# arduino_miniuno.net
KiCad netlist of a schematic drawn in EAGLE
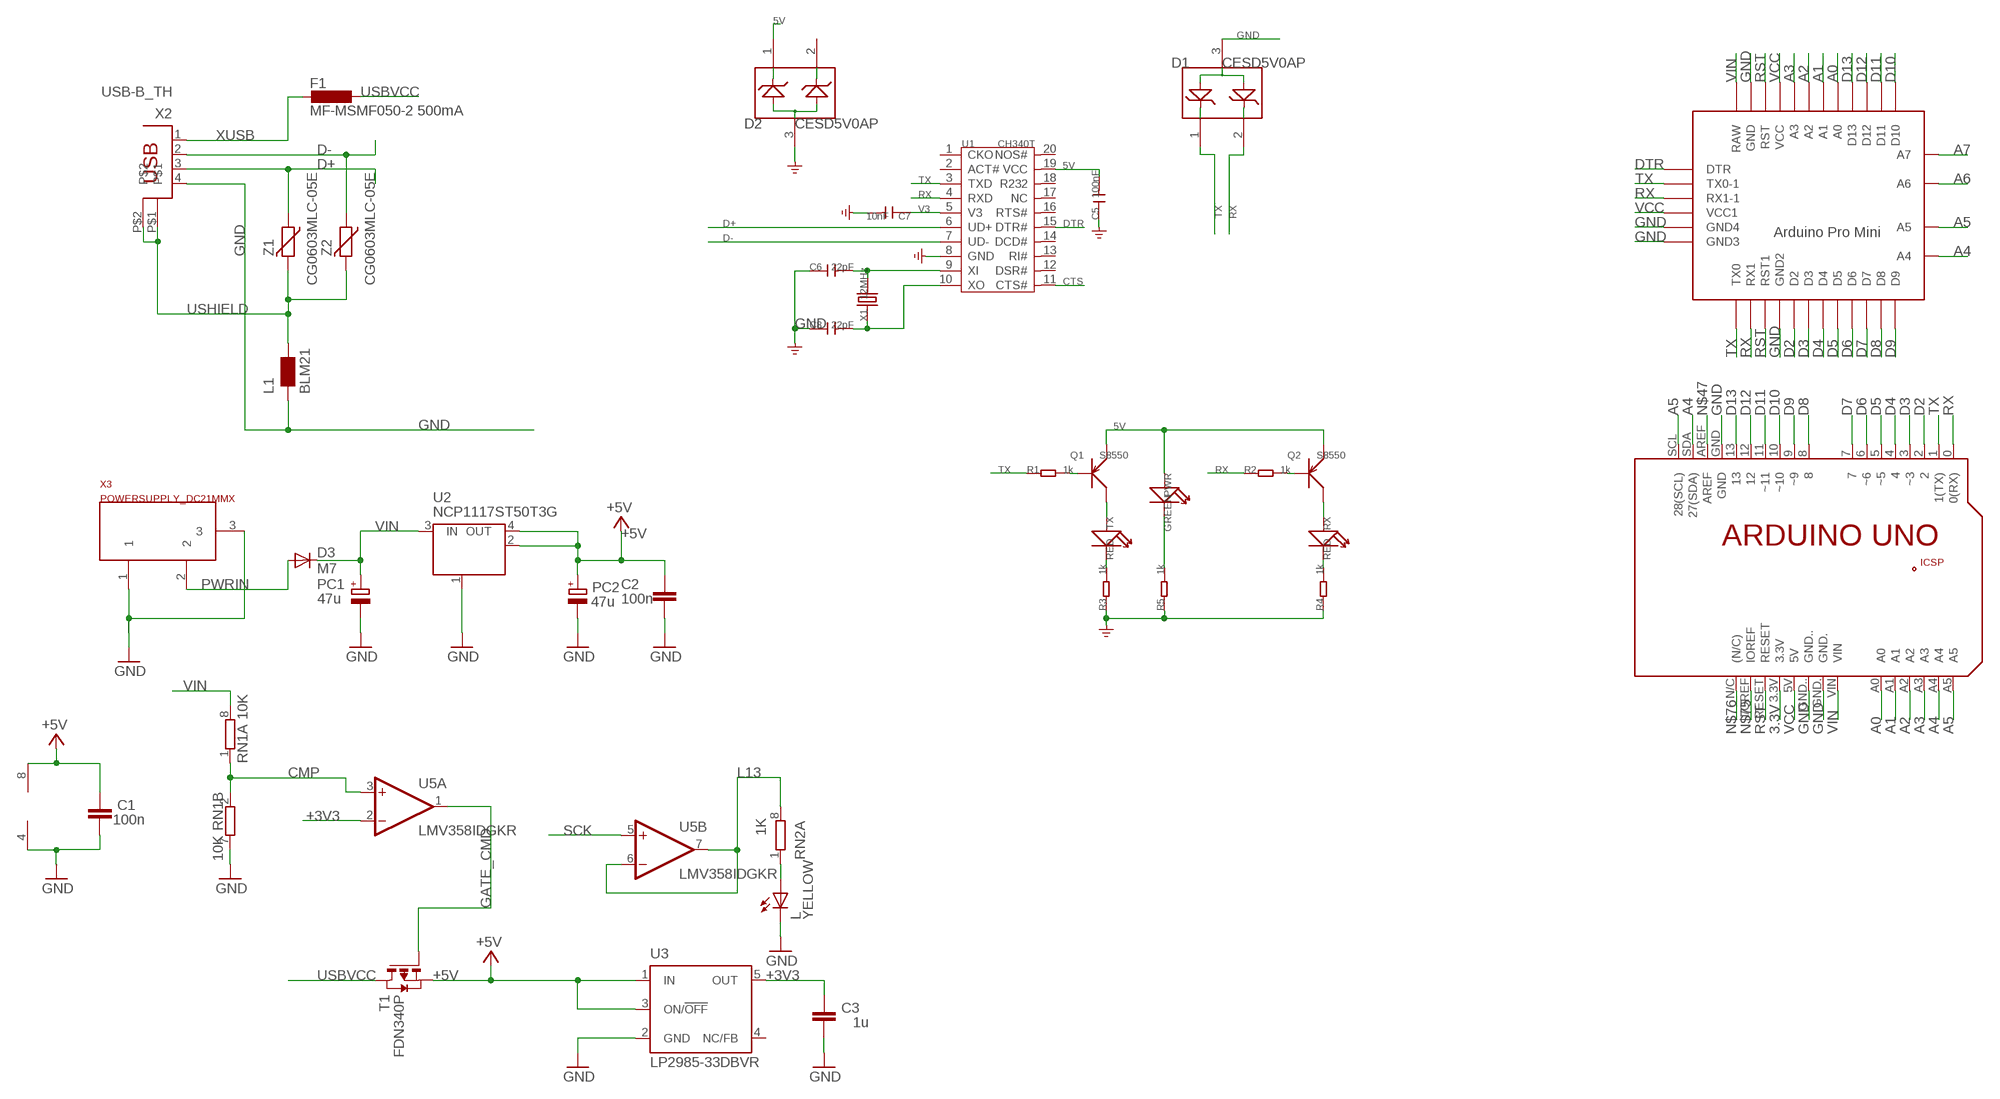
[diagram p0: schematic, sheet 1]

(export (version "E")
  (design (tool "Eeschema 10.0.6"))
  (components
    (comp (ref "C1")
      (value "100n")
      (footprint "eagle-import:C0603-ROUND")
      (libsource (lib "eagle-import") (part "C-EU0603-RND"))
    )
    (comp (ref "C2")
      (value "100n")
      (footprint "eagle-import:C0603-ROUND")
      (libsource (lib "eagle-import") (part "C-EU0603-RND"))
    )
    (comp (ref "C3")
      (value "1u")
      (footprint "eagle-import:C0603-ROUND")
      (libsource (lib "eagle-import") (part "C-EU0603-RND"))
    )
    (comp (ref "C5")
      (value "100nF")
      (footprint "eagle-import:C0402")
      (libsource (lib "eagle-import") (part "C-0402"))
    )
    (comp (ref "C6")
      (value "22pF")
      (footprint "eagle-import:C0402")
      (libsource (lib "eagle-import") (part "C-0402"))
    )
    (comp (ref "C7")
      (value "10nF")
      (footprint "eagle-import:C0402")
      (libsource (lib "eagle-import") (part "C-0402"))
    )
    (comp (ref "C8")
      (value "22pF")
      (footprint "eagle-import:C0402")
      (libsource (lib "eagle-import") (part "C-0402"))
    )
    (comp (ref "D1")
      (value "CESD5V0AP")
      (footprint "eagle-import:SOT23")
      (libsource (lib "eagle-import") (part "D-ESD-3P"))
    )
    (comp (ref "D2")
      (value "CESD5V0AP")
      (footprint "eagle-import:SOT23")
      (libsource (lib "eagle-import") (part "D-ESD-3P"))
    )
    (comp (ref "D3")
      (value "M7")
      (footprint "eagle-import:SMB")
      (libsource (lib "eagle-import") (part "DIODE-SMB"))
    )
    (comp (ref "F1")
      (value "MF-MSMF050-2 500mA")
      (footprint "eagle-import:L1812")
      (libsource (lib "eagle-import") (part "L-EUL1812"))
    )
    (comp (ref "L")
      (value "YELLOW")
      (footprint "eagle-import:CHIP-LED0805")
      (libsource (lib "eagle-import") (part "LEDCHIP-LED0805"))
    )
    (comp (ref "L1")
      (value "BLM21")
      (footprint "eagle-import:0805")
      (libsource (lib "eagle-import") (part "WE-CBF_0805"))
    )
    (comp (ref "PC1")
      (value "47u")
      (footprint "eagle-import:PANASONIC_D")
      (libsource (lib "eagle-import") (part "CPOL-EUD"))
    )
    (comp (ref "PC2")
      (value "47u")
      (footprint "eagle-import:PANASONIC_D")
      (libsource (lib "eagle-import") (part "CPOL-EUD"))
    )
    (comp (ref "PCB1")
      (value "ARDUINO_UNO")
      (footprint "eagle-import:ARDUINO_UNO")
      (libsource (lib "eagle-import") (part "ARDUINO_UNO"))
    )
    (comp (ref "PWR")
      (value "GREEN")
      (footprint "eagle-import:LED-0603")
      (libsource (lib "eagle-import") (part "LED'0603'"))
    )
    (comp (ref "Q1")
      (value "S8550")
      (footprint "eagle-import:SOT23")
      (libsource (lib "eagle-import") (part "TRANSISTOR-PNP-SOT23"))
    )
    (comp (ref "Q2")
      (value "S8550")
      (footprint "eagle-import:SOT23")
      (libsource (lib "eagle-import") (part "TRANSISTOR-PNP-SOT23"))
    )
    (comp (ref "R1")
      (value "1k")
      (footprint "eagle-import:R0402")
      (libsource (lib "eagle-import") (part "R-0402"))
    )
    (comp (ref "R2")
      (value "1k")
      (footprint "eagle-import:R0402")
      (libsource (lib "eagle-import") (part "R-0402"))
    )
    (comp (ref "R3")
      (value "1k")
      (footprint "eagle-import:R0402")
      (libsource (lib "eagle-import") (part "R-0402"))
    )
    (comp (ref "R4")
      (value "1k")
      (footprint "eagle-import:R0402")
      (libsource (lib "eagle-import") (part "R-0402"))
    )
    (comp (ref "R5")
      (value "1k")
      (footprint "eagle-import:R0402")
      (libsource (lib "eagle-import") (part "R-0402"))
    )
    (comp (ref "RN1")
      (value "10K")
      (footprint "eagle-import:CAY16")
      (libsource (lib "eagle-import") (part "4R-NCAY16"))
    )
    (comp (ref "RN2")
      (value "1K")
      (footprint "eagle-import:CAY16")
      (libsource (lib "eagle-import") (part "4R-NCAY16"))
    )
    (comp (ref "RX")
      (value "RED")
      (footprint "eagle-import:LED-0603")
      (libsource (lib "eagle-import") (part "LED'0603'"))
    )
    (comp (ref "T1")
      (value "FDN340P")
      (footprint "eagle-import:SOT-23")
      (libsource (lib "eagle-import") (part "PMOSSOT23"))
    )
    (comp (ref "TX")
      (value "RED")
      (footprint "eagle-import:LED-0603")
      (libsource (lib "eagle-import") (part "LED'0603'"))
    )
    (comp (ref "U$3")
      (value "PRO-MINI-2")
      (footprint "eagle-import:PRO-MINI-2")
      (libsource (lib "eagle-import") (part "PRO-MINI-2"))
    )
    (comp (ref "U1")
      (value "CH340T")
      (footprint "eagle-import:SSOP20")
      (libsource (lib "eagle-import") (part "CH340T"))
    )
    (comp (ref "U2")
      (value "NCP1117ST50T3G")
      (footprint "eagle-import:SOT223")
      (libsource (lib "eagle-import") (part "MC33269ST-3.3T3"))
    )
    (comp (ref "U3")
      (value "LP2985-33DBVR")
      (footprint "eagle-import:SOT23-DBV")
      (libsource (lib "eagle-import") (part "LP2985-XXDBVR33"))
    )
    (comp (ref "U5")
      (value "LMV358IDGKR")
      (footprint "eagle-import:MSOP08")
      (libsource (lib "eagle-import") (part "LMV358?MMX"))
    )
    (comp (ref "X1")
      (value "12MHz")
      (footprint "eagle-import:HC49UP")
      (libsource (lib "eagle-import") (part "CRYSTAL'HC49UP'"))
    )
    (comp (ref "X2")
      (value "USB-B_TH")
      (footprint "eagle-import:PN61729")
      (libsource (lib "eagle-import") (part "PN61729"))
    )
    (comp (ref "X3")
      (value "POWERSUPPLY_DC21MMX")
      (footprint "eagle-import:POWERSUPPLY_DC-21MM")
      (libsource (lib "eagle-import") (part "POWERSUPPLY_DC21MMX"))
    )
    (comp (ref "Z1")
      (value "CG0603MLC-05E")
      (footprint "eagle-import:CT_CN0603")
      (libsource (lib "eagle-import") (part "VARISTORCN0603"))
    )
    (comp (ref "Z2")
      (value "CG0603MLC-05E")
      (footprint "eagle-import:CT_CN0603")
      (libsource (lib "eagle-import") (part "VARISTORCN0603"))
    )
  )
  (nets
    (net (code "1") (name "+5V") (class "Default")
      (node (ref "C1") (pin "2") (pinfunction "2_2") (pintype "passive"))
      (node (ref "C2") (pin "2") (pinfunction "2_2") (pintype "passive"))
      (node (ref "PC2") (pin "+") (pinfunction "+_+") (pintype "passive"))
      (node (ref "T1") (pin "2") (pinfunction "S_2") (pintype "passive"))
      (node (ref "U2") (pin "2") (pinfunction "OUT_2") (pintype "passive"))
      (node (ref "U2") (pin "4") (pinfunction "OUT_4") (pintype "passive"))
      (node (ref "U3") (pin "1") (pinfunction "IN_1") (pintype "input"))
      (node (ref "U3") (pin "3") (pinfunction "ON/~{OFF}_3") (pintype "input"))
      (node (ref "U5") (pin "8") (pinfunction "V+_8") (pintype "power_in"))
    )
    (net (code "2") (name "/+3V3") (class "Default")
      (node (ref "C3") (pin "2") (pinfunction "2_2") (pintype "passive"))
      (node (ref "U3") (pin "5") (pinfunction "OUT_5") (pintype "passive"))
      (node (ref "U5") (pin "2") (pinfunction "-IN_2") (pintype "input"))
    )
    (net (code "3") (name "/3.3V") (class "Default")
      (node (ref "PCB1") (pin "3.3V") (pinfunction "3.3V_3.3V") (pintype "bidirectional"))
    )
    (net (code "4") (name "/5V") (class "Default")
      (node (ref "C5") (pin "2") (pinfunction "2_2") (pintype "passive"))
      (node (ref "D2") (pin "1") (pinfunction "1_1") (pintype "bidirectional"))
      (node (ref "PWR") (pin "+") (pinfunction "+_+") (pintype "passive"))
      (node (ref "Q1") (pin "2") (pinfunction "E_2") (pintype "passive"))
      (node (ref "Q2") (pin "2") (pinfunction "E_2") (pintype "passive"))
      (node (ref "U1") (pin "19") (pinfunction "VCC_19") (pintype "power_in"))
    )
    (net (code "5") (name "/A0") (class "Default")
      (node (ref "PCB1") (pin "A0") (pinfunction "A0_A0") (pintype "bidirectional"))
      (node (ref "U$3") (pin "A0") (pinfunction "A0_A0") (pintype "bidirectional"))
    )
    (net (code "6") (name "/A1") (class "Default")
      (node (ref "PCB1") (pin "A1") (pinfunction "A1_A1") (pintype "bidirectional"))
      (node (ref "U$3") (pin "A1") (pinfunction "A1_A1") (pintype "bidirectional"))
    )
    (net (code "7") (name "/A2") (class "Default")
      (node (ref "PCB1") (pin "A2") (pinfunction "A2_A2") (pintype "bidirectional"))
      (node (ref "U$3") (pin "A2") (pinfunction "A2_A2") (pintype "bidirectional"))
    )
    (net (code "8") (name "/A3") (class "Default")
      (node (ref "PCB1") (pin "A3") (pinfunction "A3_A3") (pintype "bidirectional"))
      (node (ref "U$3") (pin "A3") (pinfunction "A3_A3") (pintype "bidirectional"))
    )
    (net (code "9") (name "/A4") (class "Default")
      (node (ref "PCB1") (pin "A4") (pinfunction "A4_A4") (pintype "bidirectional"))
      (node (ref "PCB1") (pin "SDA") (pinfunction "27(SDA)_SDA") (pintype "bidirectional"))
      (node (ref "U$3") (pin "A4") (pinfunction "A4_A4") (pintype "bidirectional"))
    )
    (net (code "10") (name "/A5") (class "Default")
      (node (ref "PCB1") (pin "A5") (pinfunction "A5_A5") (pintype "bidirectional"))
      (node (ref "PCB1") (pin "SCL") (pinfunction "28(SCL)_SCL") (pintype "bidirectional"))
      (node (ref "U$3") (pin "A5") (pinfunction "A5_A5") (pintype "bidirectional"))
    )
    (net (code "11") (name "/A6") (class "Default")
      (node (ref "U$3") (pin "A6") (pinfunction "A6_A6") (pintype "bidirectional"))
    )
    (net (code "12") (name "/A7") (class "Default")
      (node (ref "U$3") (pin "A7") (pinfunction "A7_A7") (pintype "bidirectional"))
    )
    (net (code "13") (name "/CMP") (class "Default")
      (node (ref "RN1") (pin "1") (pinfunction "1_1") (pintype "passive"))
      (node (ref "RN1") (pin "2") (pinfunction "1_2") (pintype "passive"))
      (node (ref "U5") (pin "3") (pinfunction "+IN_3") (pintype "input"))
    )
    (net (code "14") (name "/CTS") (class "Default")
      (node (ref "U1") (pin "11") (pinfunction "CTS#_11") (pintype "input"))
    )
    (net (code "15") (name "/D+") (class "Default")
      (node (ref "U1") (pin "6") (pinfunction "UD+_6") (pintype "bidirectional"))
      (node (ref "X2") (pin "3") (pinfunction "3_3") (pintype "bidirectional"))
      (node (ref "Z1") (pin "1") (pinfunction "1_1") (pintype "passive"))
    )
    (net (code "16") (name "/D-") (class "Default")
      (node (ref "U1") (pin "7") (pinfunction "UD-_7") (pintype "bidirectional"))
      (node (ref "X2") (pin "2") (pinfunction "2_2") (pintype "bidirectional"))
      (node (ref "Z2") (pin "1") (pinfunction "1_1") (pintype "passive"))
    )
    (net (code "17") (name "/D2") (class "Default")
      (node (ref "PCB1") (pin "2") (pinfunction "2_2") (pintype "bidirectional"))
      (node (ref "U$3") (pin "D2") (pinfunction "D2_D2") (pintype "bidirectional"))
    )
    (net (code "18") (name "/D3") (class "Default")
      (node (ref "PCB1") (pin "3") (pinfunction "~{3}_3") (pintype "bidirectional"))
      (node (ref "U$3") (pin "D3") (pinfunction "D3_D3") (pintype "bidirectional"))
    )
    (net (code "19") (name "/D4") (class "Default")
      (node (ref "PCB1") (pin "4") (pinfunction "4_4") (pintype "bidirectional"))
      (node (ref "U$3") (pin "D4") (pinfunction "D4_D4") (pintype "bidirectional"))
    )
    (net (code "20") (name "/D5") (class "Default")
      (node (ref "PCB1") (pin "5") (pinfunction "~{5}_5") (pintype "bidirectional"))
      (node (ref "U$3") (pin "D5") (pinfunction "D5_D5") (pintype "bidirectional"))
    )
    (net (code "21") (name "/D6") (class "Default")
      (node (ref "PCB1") (pin "6") (pinfunction "~{6}_6") (pintype "bidirectional"))
      (node (ref "U$3") (pin "D6") (pinfunction "D6_D6") (pintype "bidirectional"))
    )
    (net (code "22") (name "/D7") (class "Default")
      (node (ref "PCB1") (pin "7") (pinfunction "7_7") (pintype "bidirectional"))
      (node (ref "U$3") (pin "D7") (pinfunction "D7_D7") (pintype "bidirectional"))
    )
    (net (code "23") (name "/D8") (class "Default")
      (node (ref "PCB1") (pin "8") (pinfunction "8_8") (pintype "bidirectional"))
      (node (ref "U$3") (pin "D8") (pinfunction "D8_D8") (pintype "bidirectional"))
    )
    (net (code "24") (name "/D9") (class "Default")
      (node (ref "PCB1") (pin "9") (pinfunction "~{9}_9") (pintype "bidirectional"))
      (node (ref "U$3") (pin "D9") (pinfunction "D9_D9") (pintype "bidirectional"))
    )
    (net (code "25") (name "/D10") (class "Default")
      (node (ref "PCB1") (pin "10") (pinfunction "~{10}_10") (pintype "bidirectional"))
      (node (ref "U$3") (pin "D10") (pinfunction "D10_D10") (pintype "bidirectional"))
    )
    (net (code "26") (name "/D11") (class "Default")
      (node (ref "PCB1") (pin "11") (pinfunction "~{11}_11") (pintype "bidirectional"))
      (node (ref "U$3") (pin "D11") (pinfunction "D11_D11") (pintype "bidirectional"))
    )
    (net (code "27") (name "/D12") (class "Default")
      (node (ref "PCB1") (pin "12") (pinfunction "12_12") (pintype "bidirectional"))
      (node (ref "U$3") (pin "D12") (pinfunction "D12_D12") (pintype "bidirectional"))
    )
    (net (code "28") (name "/D13") (class "Default")
      (node (ref "PCB1") (pin "13") (pinfunction "13_13") (pintype "bidirectional"))
      (node (ref "U$3") (pin "D13") (pinfunction "D13_D13") (pintype "bidirectional"))
    )
    (net (code "29") (name "/DTR") (class "Default")
      (node (ref "U$3") (pin "DTR") (pinfunction "DTR_DTR") (pintype "bidirectional"))
      (node (ref "U1") (pin "15") (pinfunction "DTR#_15") (pintype "output"))
    )
    (net (code "30") (name "/GATE_CMD") (class "Default")
      (node (ref "T1") (pin "3") (pinfunction "G_3") (pintype "passive"))
      (node (ref "U5") (pin "1") (pinfunction "OUT_1") (pintype "output"))
    )
    (net (code "31") (name "/L13") (class "Default")
      (node (ref "RN2") (pin "8") (pinfunction "2_8") (pintype "passive"))
      (node (ref "U5") (pin "6") (pinfunction "-IN_6") (pintype "input"))
      (node (ref "U5") (pin "7") (pinfunction "OUT_7") (pintype "output"))
    )
    (net (code "32") (name "/N$47") (class "Default")
      (node (ref "PCB1") (pin "AREF") (pinfunction "AREF_AREF") (pintype "bidirectional"))
    )
    (net (code "33") (name "/N$75") (class "Default")
      (node (ref "PCB1") (pin "I/OREF") (pinfunction "IOREF_I/OREF") (pintype "bidirectional"))
    )
    (net (code "34") (name "/N$76") (class "Default")
      (node (ref "PCB1") (pin "N/C") (pinfunction "(N/C)_N/C") (pintype "bidirectional"))
    )
    (net (code "35") (name "/NOS#") (class "Default")
      (node (ref "U1") (pin "20") (pinfunction "NOS#_20") (pintype "power_in"))
    )
    (net (code "36") (name "/PWRIN") (class "Default")
      (node (ref "D3") (pin "A") (pinfunction "A_A") (pintype "passive"))
      (node (ref "X3") (pin "2") (pinfunction "2_2") (pintype "power_in"))
    )
    (net (code "37") (name "/RST") (class "Default")
      (node (ref "PCB1") (pin "RESET") (pinfunction "RESET_RESET") (pintype "bidirectional"))
      (node (ref "U$3") (pin "RST") (pinfunction "RST_RST") (pintype "bidirectional"))
      (node (ref "U$3") (pin "RST1") (pinfunction "RST1_RST1") (pintype "bidirectional"))
    )
    (net (code "38") (name "/RX") (class "Default")
      (node (ref "D1") (pin "2") (pinfunction "2_2") (pintype "bidirectional"))
      (node (ref "PCB1") (pin "0") (pinfunction "0(RX)_0") (pintype "bidirectional"))
      (node (ref "R2") (pin "1") (pinfunction "1_1") (pintype "passive"))
      (node (ref "U$3") (pin "RX1") (pinfunction "RX1_RX1") (pintype "bidirectional"))
      (node (ref "U$3") (pin "RX1-1") (pinfunction "RX1-1_RX1-1") (pintype "bidirectional"))
      (node (ref "U1") (pin "4") (pinfunction "RXD_4") (pintype "input"))
    )
    (net (code "39") (name "/SCK") (class "Default")
      (node (ref "U5") (pin "5") (pinfunction "+IN_5") (pintype "input"))
    )
    (net (code "40") (name "/TX") (class "Default")
      (node (ref "D1") (pin "1") (pinfunction "1_1") (pintype "bidirectional"))
      (node (ref "PCB1") (pin "1") (pinfunction "1(TX)_1") (pintype "bidirectional"))
      (node (ref "R1") (pin "1") (pinfunction "1_1") (pintype "passive"))
      (node (ref "U$3") (pin "TX0") (pinfunction "TX0_TX0") (pintype "bidirectional"))
      (node (ref "U$3") (pin "TX0-1") (pinfunction "TX0-1_TX0-1") (pintype "bidirectional"))
      (node (ref "U1") (pin "3") (pinfunction "TXD_3") (pintype "output"))
    )
    (net (code "41") (name "/USBVCC") (class "Default")
      (node (ref "F1") (pin "1") (pinfunction "1_1") (pintype "passive"))
      (node (ref "T1") (pin "1") (pinfunction "D_1") (pintype "passive"))
    )
    (net (code "42") (name "/USHIELD") (class "Default")
      (node (ref "L1") (pin "2") (pinfunction "2_2") (pintype "passive"))
      (node (ref "X2") (pin "P$1") (pinfunction "P$1_P$1") (pintype "bidirectional"))
      (node (ref "X2") (pin "P$2") (pinfunction "P$2_P$2") (pintype "bidirectional"))
      (node (ref "Z1") (pin "2") (pinfunction "2_2") (pintype "passive"))
      (node (ref "Z2") (pin "2") (pinfunction "2_2") (pintype "passive"))
    )
    (net (code "43") (name "/V3") (class "Default")
      (node (ref "C7") (pin "1") (pinfunction "1_1") (pintype "passive"))
      (node (ref "U1") (pin "5") (pinfunction "V3_5") (pintype "power_in"))
    )
    (net (code "44") (name "/VCC") (class "Default")
      (node (ref "PCB1") (pin "5V") (pinfunction "5V_5V") (pintype "bidirectional"))
      (node (ref "U$3") (pin "VCC") (pinfunction "VCC_VCC") (pintype "bidirectional"))
      (node (ref "U$3") (pin "VCC1") (pinfunction "VCC1_VCC1") (pintype "bidirectional"))
    )
    (net (code "45") (name "/VIN") (class "Default")
      (node (ref "D3") (pin "C") (pinfunction "C_C") (pintype "passive"))
      (node (ref "PC1") (pin "+") (pinfunction "+_+") (pintype "passive"))
      (node (ref "PCB1") (pin "VIN") (pinfunction "VIN_VIN") (pintype "bidirectional"))
      (node (ref "RN1") (pin "8") (pinfunction "2_8") (pintype "passive"))
      (node (ref "U$3") (pin "RAW") (pinfunction "RAW_RAW") (pintype "bidirectional"))
      (node (ref "U2") (pin "3") (pinfunction "IN_3") (pintype "input"))
    )
    (net (code "46") (name "/XUSB") (class "Default")
      (node (ref "F1") (pin "2") (pinfunction "2_2") (pintype "passive"))
      (node (ref "X2") (pin "1") (pinfunction "1_1") (pintype "bidirectional"))
    )
    (net (code "47") (name "GND") (class "Default")
      (node (ref "C1") (pin "1") (pinfunction "1_1") (pintype "passive"))
      (node (ref "C2") (pin "1") (pinfunction "1_1") (pintype "passive"))
      (node (ref "C3") (pin "1") (pinfunction "1_1") (pintype "passive"))
      (node (ref "C5") (pin "1") (pinfunction "1_1") (pintype "passive"))
      (node (ref "C6") (pin "1") (pinfunction "1_1") (pintype "passive"))
      (node (ref "C7") (pin "2") (pinfunction "2_2") (pintype "passive"))
      (node (ref "C8") (pin "1") (pinfunction "1_1") (pintype "passive"))
      (node (ref "D1") (pin "3") (pinfunction "3_3") (pintype "bidirectional"))
      (node (ref "D2") (pin "3") (pinfunction "3_3") (pintype "bidirectional"))
      (node (ref "L") (pin "C") (pinfunction "C_C") (pintype "passive"))
      (node (ref "L1") (pin "1") (pinfunction "1_1") (pintype "passive"))
      (node (ref "PC1") (pin "-") (pinfunction "-_-") (pintype "passive"))
      (node (ref "PC2") (pin "-") (pinfunction "-_-") (pintype "passive"))
      (node (ref "PCB1") (pin "GND") (pinfunction "GND_GND") (pintype "bidirectional"))
      (node (ref "PCB1") (pin "GND.") (pinfunction "GND._GND.") (pintype "bidirectional"))
      (node (ref "PCB1") (pin "GND..") (pinfunction "GND.._GND..") (pintype "bidirectional"))
      (node (ref "R3") (pin "1") (pinfunction "1_1") (pintype "passive"))
      (node (ref "R4") (pin "1") (pinfunction "1_1") (pintype "passive"))
      (node (ref "R5") (pin "1") (pinfunction "1_1") (pintype "passive"))
      (node (ref "RN1") (pin "7") (pinfunction "2_7") (pintype "passive"))
      (node (ref "U$3") (pin "GND") (pinfunction "GND_GND") (pintype "bidirectional"))
      (node (ref "U$3") (pin "GND1") (pinfunction "GND2_GND1") (pintype "bidirectional"))
      (node (ref "U$3") (pin "GND2") (pinfunction "GND3_GND2") (pintype "bidirectional"))
      (node (ref "U$3") (pin "GND3") (pinfunction "GND4_GND3") (pintype "bidirectional"))
      (node (ref "U1") (pin "8") (pinfunction "GND_8") (pintype "power_in"))
      (node (ref "U2") (pin "1") (pinfunction "GND/ADJ_1") (pintype "input"))
      (node (ref "U3") (pin "2") (pinfunction "GND_2") (pintype "power_in"))
      (node (ref "U5") (pin "4") (pinfunction "V-_4") (pintype "power_in"))
      (node (ref "X2") (pin "4") (pinfunction "4_4") (pintype "bidirectional"))
      (node (ref "X3") (pin "1") (pinfunction "1_1") (pintype "power_in"))
      (node (ref "X3") (pin "3") (pinfunction "3_3") (pintype "power_in"))
    )
    (net (code "48") (name "Net-(L-PadA)") (class "Default")
      (node (ref "L") (pin "A") (pinfunction "A_A") (pintype "passive"))
      (node (ref "RN2") (pin "1") (pinfunction "1_1") (pintype "passive"))
    )
    (net (code "49") (name "Net-(PWR-Pad-)") (class "Default")
      (node (ref "PWR") (pin "-") (pinfunction "-_-") (pintype "passive"))
      (node (ref "R5") (pin "2") (pinfunction "2_2") (pintype "passive"))
    )
    (net (code "50") (name "Net-(Q1-B)") (class "Default")
      (node (ref "Q1") (pin "1") (pinfunction "B_1") (pintype "passive"))
      (node (ref "R1") (pin "2") (pinfunction "2_2") (pintype "passive"))
    )
    (net (code "51") (name "Net-(Q1-C)") (class "Default")
      (node (ref "Q1") (pin "3") (pinfunction "C_3") (pintype "passive"))
      (node (ref "TX") (pin "+") (pinfunction "+_+") (pintype "passive"))
    )
    (net (code "52") (name "Net-(Q2-B)") (class "Default")
      (node (ref "Q2") (pin "1") (pinfunction "B_1") (pintype "passive"))
      (node (ref "R2") (pin "2") (pinfunction "2_2") (pintype "passive"))
    )
    (net (code "53") (name "Net-(Q2-C)") (class "Default")
      (node (ref "Q2") (pin "3") (pinfunction "C_3") (pintype "passive"))
      (node (ref "RX") (pin "+") (pinfunction "+_+") (pintype "passive"))
    )
    (net (code "54") (name "Net-(R3-Pad2)") (class "Default")
      (node (ref "R3") (pin "2") (pinfunction "2_2") (pintype "passive"))
      (node (ref "TX") (pin "-") (pinfunction "-_-") (pintype "passive"))
    )
    (net (code "55") (name "Net-(R4-Pad2)") (class "Default")
      (node (ref "R4") (pin "2") (pinfunction "2_2") (pintype "passive"))
      (node (ref "RX") (pin "-") (pinfunction "-_-") (pintype "passive"))
    )
    (net (code "56") (name "Net-(U1-XI)") (class "Default")
      (node (ref "C6") (pin "2") (pinfunction "2_2") (pintype "passive"))
      (node (ref "U1") (pin "9") (pinfunction "XI_9") (pintype "input"))
      (node (ref "X1") (pin "2") (pinfunction "2_2") (pintype "passive"))
    )
    (net (code "57") (name "Net-(U1-XO)") (class "Default")
      (node (ref "C8") (pin "2") (pinfunction "2_2") (pintype "passive"))
      (node (ref "U1") (pin "10") (pinfunction "XO_10") (pintype "output"))
      (node (ref "X1") (pin "1") (pinfunction "1_1") (pintype "passive"))
    )
    (net (code "58") (name "unconnected-(D2-Pad2)") (class "Default")
      (node (ref "D2") (pin "2") (pinfunction "2_2") (pintype "bidirectional"))
    )
    (net (code "59") (name "unconnected-(PCB1-Pad+5V)") (class "Default")
      (node (ref "PCB1") (pin "+5V") (pinfunction "+5V_+5V") (pintype "bidirectional"))
    )
    (net (code "60") (name "unconnected-(PCB1-PadGND_)") (class "Default")
      (node (ref "PCB1") (pin "GND_") (pinfunction "GND__GND_") (pintype "bidirectional"))
    )
    (net (code "61") (name "unconnected-(PCB1-PadMISO)") (class "Default")
      (node (ref "PCB1") (pin "MISO") (pinfunction "MISO_MISO") (pintype "bidirectional"))
    )
    (net (code "62") (name "unconnected-(PCB1-PadMOSI)") (class "Default")
      (node (ref "PCB1") (pin "MOSI") (pinfunction "MOSI_MOSI") (pintype "bidirectional"))
    )
    (net (code "63") (name "unconnected-(PCB1-PadRESET.)") (class "Default")
      (node (ref "PCB1") (pin "RESET.") (pinfunction "RESET._RESET.") (pintype "bidirectional"))
    )
    (net (code "64") (name "unconnected-(PCB1-PadSCK)") (class "Default")
      (node (ref "PCB1") (pin "SCK") (pinfunction "SCK_SCK") (pintype "bidirectional"))
    )
    (net (code "65") (name "unconnected-(U1-ACT#-Pad2)") (class "Default")
      (node (ref "U1") (pin "2") (pinfunction "ACT#_2") (pintype "output"))
    )
    (net (code "66") (name "unconnected-(U1-CKO-Pad1)") (class "Default")
      (node (ref "U1") (pin "1") (pinfunction "CKO_1") (pintype "output"))
    )
    (net (code "67") (name "unconnected-(U1-DCD#-Pad14)") (class "Default")
      (node (ref "U1") (pin "14") (pinfunction "DCD#_14") (pintype "input"))
    )
    (net (code "68") (name "unconnected-(U1-DSR#-Pad12)") (class "Default")
      (node (ref "U1") (pin "12") (pinfunction "DSR#_12") (pintype "input"))
    )
    (net (code "69") (name "unconnected-(U1-NC-Pad17)") (class "Default")
      (node (ref "U1") (pin "17") (pinfunction "NC_17") (pintype "no_connect"))
    )
    (net (code "70") (name "unconnected-(U1-R232-Pad18)") (class "Default")
      (node (ref "U1") (pin "18") (pinfunction "R232_18") (pintype "input"))
    )
    (net (code "71") (name "unconnected-(U1-RI#-Pad13)") (class "Default")
      (node (ref "U1") (pin "13") (pinfunction "RI#_13") (pintype "input"))
    )
    (net (code "72") (name "unconnected-(U1-RTS#-Pad16)") (class "Default")
      (node (ref "U1") (pin "16") (pinfunction "RTS#_16") (pintype "output"))
    )
    (net (code "73") (name "unconnected-(U3-NC{slash}FB-Pad4)") (class "Default")
      (node (ref "U3") (pin "4") (pinfunction "NC/FB_4") (pintype "passive"))
    )
  )
)
